# NixieClock_Modified2.net
KiCad netlist of a schematic drawn in EAGLE
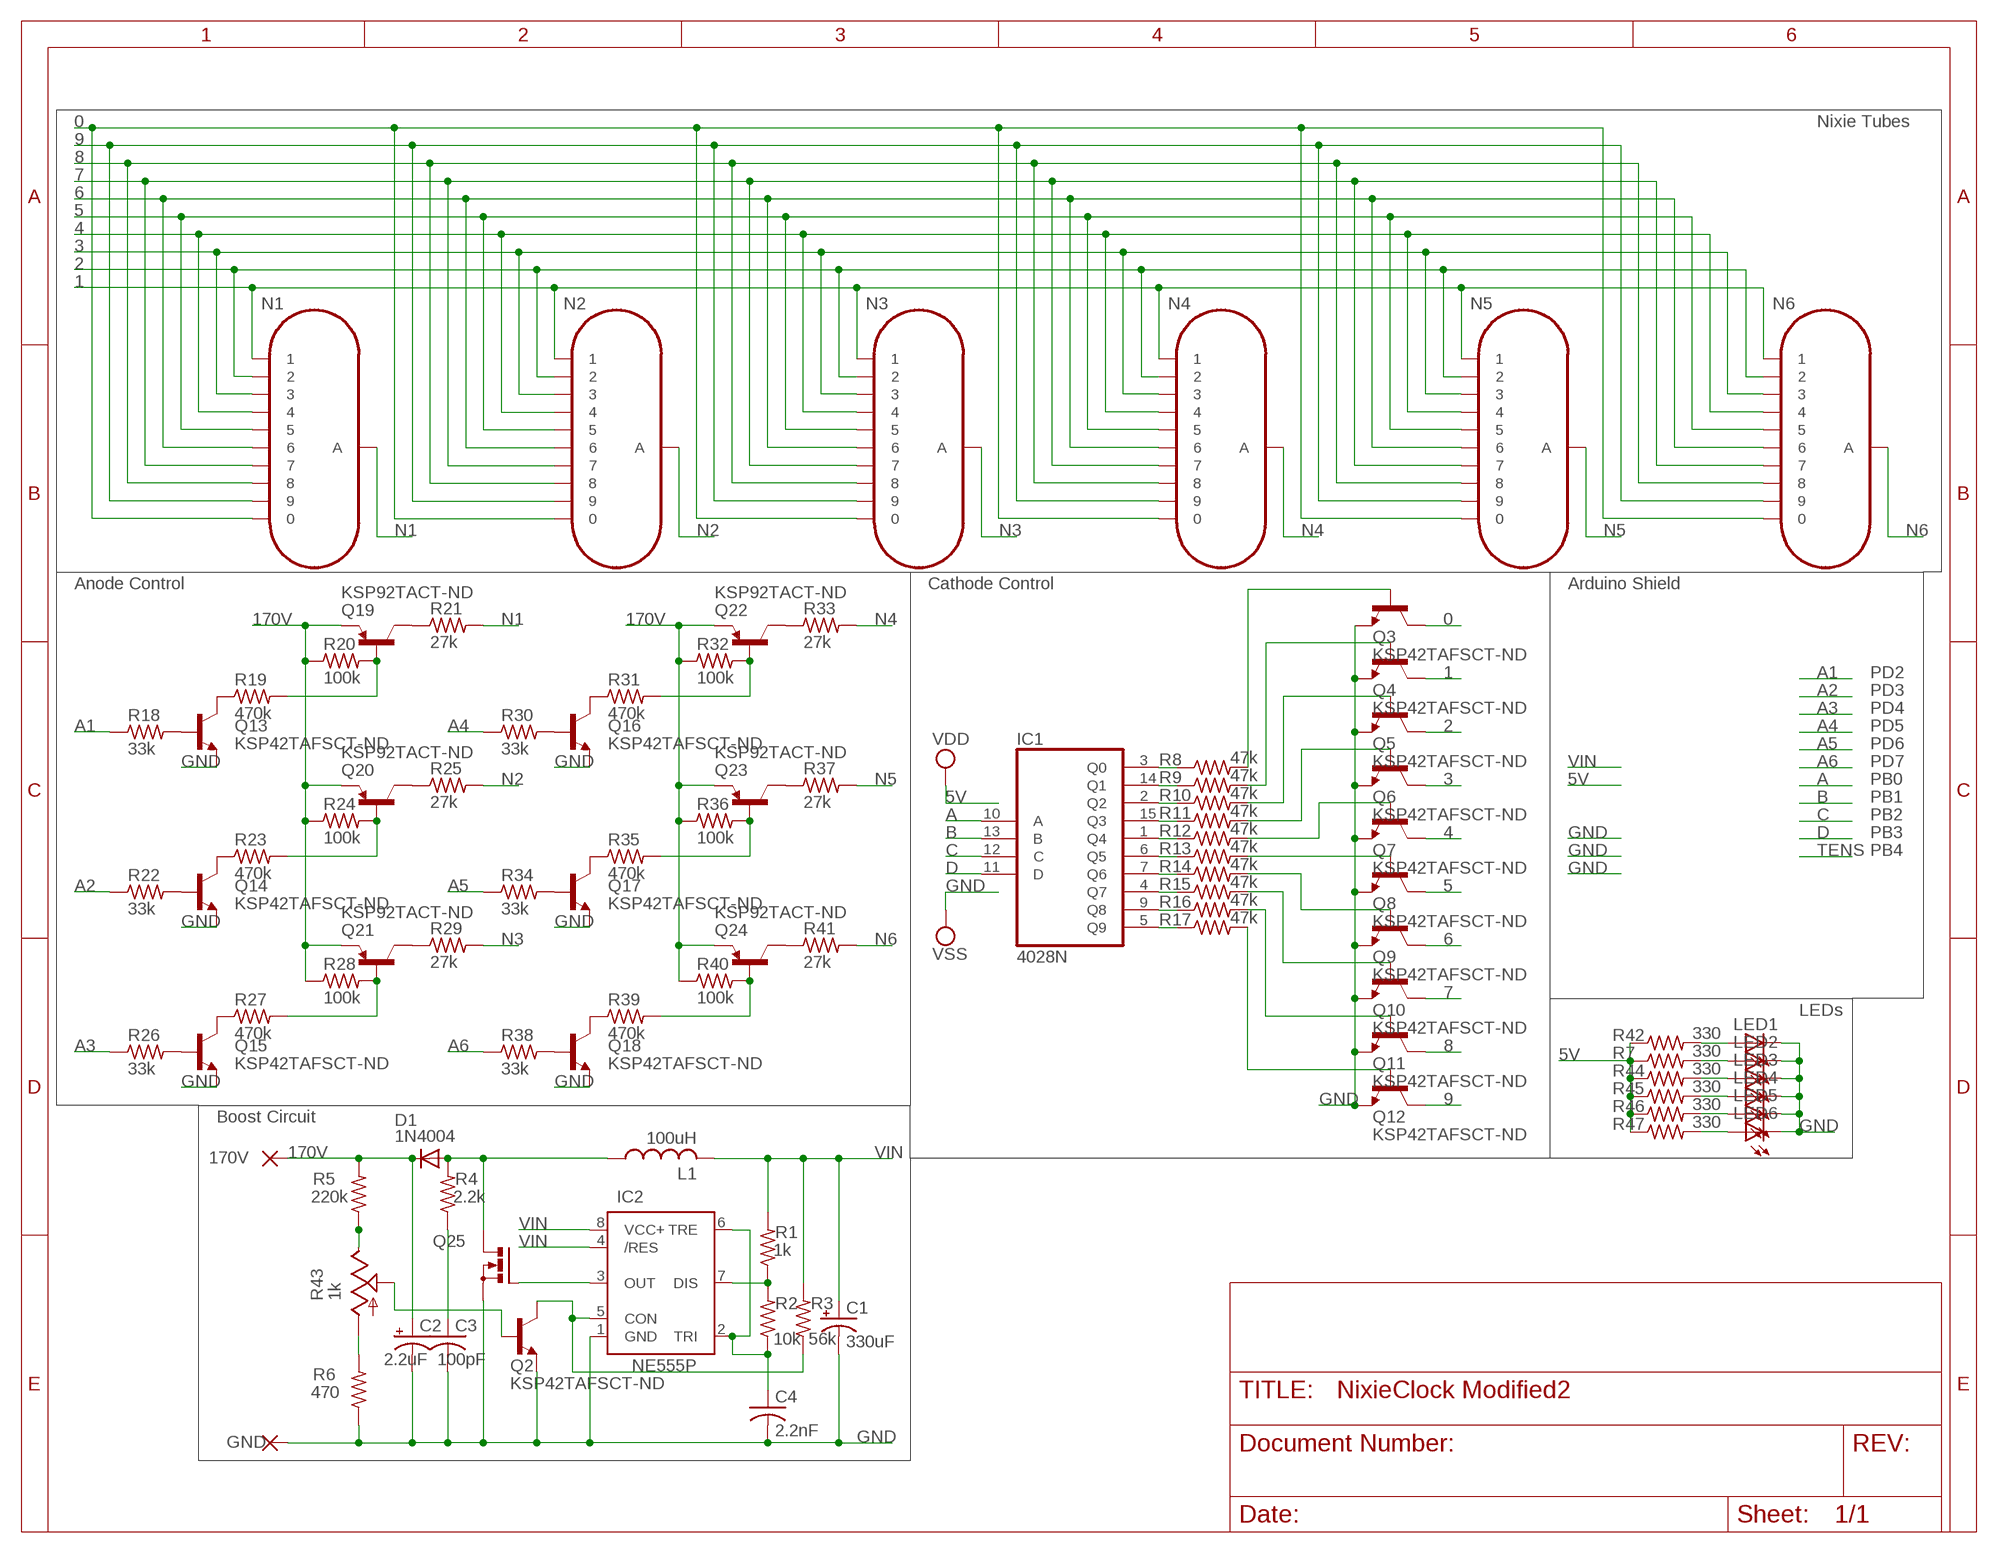
[diagram p0: schematic, sheet 1]

(export (version "E")
  (design (tool "Eeschema 10.0.6"))
  (components
    (comp (ref "C1")
      (value "330uF")
      (footprint "eagle-import:E2,5-6E")
      (libsource (lib "eagle-import") (part "CPOL-USE2,5-6E"))
    )
    (comp (ref "C2")
      (value "2.2uF")
      (footprint "eagle-import:E2,5-6E")
      (libsource (lib "eagle-import") (part "CPOL-USE2,5-6E"))
    )
    (comp (ref "C3")
      (value "100pF")
      (footprint "eagle-import:C050-025X075")
      (libsource (lib "eagle-import") (part "C-US050-025X075"))
    )
    (comp (ref "C4")
      (value "2.2nF")
      (footprint "eagle-import:C025-025X050")
      (libsource (lib "eagle-import") (part "resistor_C-US025-025X050"))
    )
    (comp (ref "D1")
      (value "1N4004")
      (footprint "eagle-import:DO41-10")
      (libsource (lib "eagle-import") (part "1N4004"))
    )
    (comp (ref "IC1")
      (value "4028N")
      (footprint "eagle-import:DIL16")
      (libsource (lib "eagle-import") (part "4028N"))
    )
    (comp (ref "IC2")
      (value "NE555P")
      (footprint "eagle-import:DIL-08")
      (fields (field (name "MF") "Arrow Electronics") (field (name "MPN") "NE555N"))
      (libsource (lib "eagle-import") (part "NE555P"))
    )
    (comp (ref "L1")
      (value "100uH")
      (footprint "eagle-import:6000-XXXX-RC")
      (libsource (lib "eagle-import") (part "L-US6000-XXX-RC"))
    )
    (comp (ref "LED1")
      (value "LEDCHIPLED_1206")
      (footprint "eagle-import:CHIPLED_1206")
      (libsource (lib "eagle-import") (part "LEDCHIPLED_1206"))
    )
    (comp (ref "LED2")
      (value "LEDCHIPLED_1206")
      (footprint "eagle-import:CHIPLED_1206")
      (libsource (lib "eagle-import") (part "LEDCHIPLED_1206"))
    )
    (comp (ref "LED3")
      (value "LEDCHIPLED_1206")
      (footprint "eagle-import:CHIPLED_1206")
      (libsource (lib "eagle-import") (part "LEDCHIPLED_1206"))
    )
    (comp (ref "LED4")
      (value "LEDCHIPLED_1206")
      (footprint "eagle-import:CHIPLED_1206")
      (libsource (lib "eagle-import") (part "LEDCHIPLED_1206"))
    )
    (comp (ref "LED5")
      (value "LEDCHIPLED_1206")
      (footprint "eagle-import:CHIPLED_1206")
      (libsource (lib "eagle-import") (part "LEDCHIPLED_1206"))
    )
    (comp (ref "LED6")
      (value "LEDCHIPLED_1206")
      (footprint "eagle-import:CHIPLED_1206")
      (libsource (lib "eagle-import") (part "LEDCHIPLED_1206"))
    )
    (comp (ref "N1")
      (value "IN-17")
      (footprint "eagle-import:IN-17")
      (libsource (lib "eagle-import") (part "IN-17"))
    )
    (comp (ref "N2")
      (value "IN-17")
      (footprint "eagle-import:IN-17")
      (libsource (lib "eagle-import") (part "IN-17"))
    )
    (comp (ref "N3")
      (value "IN-17")
      (footprint "eagle-import:IN-17")
      (libsource (lib "eagle-import") (part "IN-17"))
    )
    (comp (ref "N4")
      (value "IN-17")
      (footprint "eagle-import:IN-17")
      (libsource (lib "eagle-import") (part "IN-17"))
    )
    (comp (ref "N5")
      (value "IN-17")
      (footprint "eagle-import:IN-17")
      (libsource (lib "eagle-import") (part "IN-17"))
    )
    (comp (ref "N6")
      (value "IN-17")
      (footprint "eagle-import:IN-17")
      (libsource (lib "eagle-import") (part "IN-17"))
    )
    (comp (ref "PAD13")
      (value "GND")
      (footprint "eagle-import:1,6_0,8")
      (libsource (lib "eagle-import") (part "1,6/0,8"))
    )
    (comp (ref "PAD14")
      (value "170V")
      (footprint "eagle-import:1,6_0,8")
      (libsource (lib "eagle-import") (part "1,6/0,8"))
    )
    (comp (ref "Q2")
      (value "KSP42TAFSCT-ND")
      (footprint "eagle-import:TO-92-AMMO")
      (libsource (lib "eagle-import") (part "TRANSISTOR_NPNTO-92-AMMO"))
    )
    (comp (ref "Q3")
      (value "KSP42TAFSCT-ND")
      (footprint "eagle-import:TO-92-AMMO")
      (libsource (lib "eagle-import") (part "TRANSISTOR_NPNTO-92-AMMO"))
    )
    (comp (ref "Q4")
      (value "KSP42TAFSCT-ND")
      (footprint "eagle-import:TO-92-AMMO")
      (libsource (lib "eagle-import") (part "TRANSISTOR_NPNTO-92-AMMO"))
    )
    (comp (ref "Q5")
      (value "KSP42TAFSCT-ND")
      (footprint "eagle-import:TO-92-AMMO")
      (libsource (lib "eagle-import") (part "TRANSISTOR_NPNTO-92-AMMO"))
    )
    (comp (ref "Q6")
      (value "KSP42TAFSCT-ND")
      (footprint "eagle-import:TO-92-AMMO")
      (libsource (lib "eagle-import") (part "TRANSISTOR_NPNTO-92-AMMO"))
    )
    (comp (ref "Q7")
      (value "KSP42TAFSCT-ND")
      (footprint "eagle-import:TO-92-AMMO")
      (libsource (lib "eagle-import") (part "TRANSISTOR_NPNTO-92-AMMO"))
    )
    (comp (ref "Q8")
      (value "KSP42TAFSCT-ND")
      (footprint "eagle-import:TO-92-AMMO")
      (libsource (lib "eagle-import") (part "TRANSISTOR_NPNTO-92-AMMO"))
    )
    (comp (ref "Q9")
      (value "KSP42TAFSCT-ND")
      (footprint "eagle-import:TO-92-AMMO")
      (libsource (lib "eagle-import") (part "TRANSISTOR_NPNTO-92-AMMO"))
    )
    (comp (ref "Q10")
      (value "KSP42TAFSCT-ND")
      (footprint "eagle-import:TO-92-AMMO")
      (libsource (lib "eagle-import") (part "TRANSISTOR_NPNTO-92-AMMO"))
    )
    (comp (ref "Q11")
      (value "KSP42TAFSCT-ND")
      (footprint "eagle-import:TO-92-AMMO")
      (libsource (lib "eagle-import") (part "TRANSISTOR_NPNTO-92-AMMO"))
    )
    (comp (ref "Q12")
      (value "KSP42TAFSCT-ND")
      (footprint "eagle-import:TO-92-AMMO")
      (libsource (lib "eagle-import") (part "TRANSISTOR_NPNTO-92-AMMO"))
    )
    (comp (ref "Q13")
      (value "KSP42TAFSCT-ND")
      (footprint "eagle-import:TO-92-AMMO")
      (libsource (lib "eagle-import") (part "TRANSISTOR_NPNTO-92-AMMO"))
    )
    (comp (ref "Q14")
      (value "KSP42TAFSCT-ND")
      (footprint "eagle-import:TO-92-AMMO")
      (libsource (lib "eagle-import") (part "TRANSISTOR_NPNTO-92-AMMO"))
    )
    (comp (ref "Q15")
      (value "KSP42TAFSCT-ND")
      (footprint "eagle-import:TO-92-AMMO")
      (libsource (lib "eagle-import") (part "TRANSISTOR_NPNTO-92-AMMO"))
    )
    (comp (ref "Q16")
      (value "KSP42TAFSCT-ND")
      (footprint "eagle-import:TO-92-AMMO")
      (libsource (lib "eagle-import") (part "TRANSISTOR_NPNTO-92-AMMO"))
    )
    (comp (ref "Q17")
      (value "KSP42TAFSCT-ND")
      (footprint "eagle-import:TO-92-AMMO")
      (libsource (lib "eagle-import") (part "TRANSISTOR_NPNTO-92-AMMO"))
    )
    (comp (ref "Q18")
      (value "KSP42TAFSCT-ND")
      (footprint "eagle-import:TO-92-AMMO")
      (libsource (lib "eagle-import") (part "TRANSISTOR_NPNTO-92-AMMO"))
    )
    (comp (ref "Q19")
      (value "KSP92TACT-ND")
      (footprint "eagle-import:TO-92-AMMO")
      (libsource (lib "eagle-import") (part "TRANSISTOR_PNP"))
    )
    (comp (ref "Q20")
      (value "KSP92TACT-ND")
      (footprint "eagle-import:TO-92-AMMO")
      (libsource (lib "eagle-import") (part "TRANSISTOR_PNP"))
    )
    (comp (ref "Q21")
      (value "KSP92TACT-ND")
      (footprint "eagle-import:TO-92-AMMO")
      (libsource (lib "eagle-import") (part "TRANSISTOR_PNP"))
    )
    (comp (ref "Q22")
      (value "KSP92TACT-ND")
      (footprint "eagle-import:TO-92-AMMO")
      (libsource (lib "eagle-import") (part "TRANSISTOR_PNP"))
    )
    (comp (ref "Q23")
      (value "KSP92TACT-ND")
      (footprint "eagle-import:TO-92-AMMO")
      (libsource (lib "eagle-import") (part "TRANSISTOR_PNP"))
    )
    (comp (ref "Q24")
      (value "KSP92TACT-ND")
      (footprint "eagle-import:TO-92-AMMO")
      (libsource (lib "eagle-import") (part "TRANSISTOR_PNP"))
    )
    (comp (ref "Q25")
      (value "PMOSFET_NTO220BH")
      (footprint "eagle-import:TO220BH")
      (libsource (lib "eagle-import") (part "PMOSFET_NTO220BH"))
    )
    (comp (ref "R1")
      (value "1k")
      (footprint "eagle-import:0204_5")
      (libsource (lib "eagle-import") (part "R-US_0204/5"))
    )
    (comp (ref "R2")
      (value "10k")
      (footprint "eagle-import:0204_5")
      (libsource (lib "eagle-import") (part "R-US_0204/5"))
    )
    (comp (ref "R3")
      (value "56k")
      (footprint "eagle-import:0204_5")
      (libsource (lib "eagle-import") (part "R-US_0204/5"))
    )
    (comp (ref "R4")
      (value "2.2k")
      (footprint "eagle-import:0204_5")
      (libsource (lib "eagle-import") (part "R-US_0204/5"))
    )
    (comp (ref "R5")
      (value "220k")
      (footprint "eagle-import:0204_5")
      (libsource (lib "eagle-import") (part "R-US_0204/5"))
    )
    (comp (ref "R6")
      (value "470")
      (footprint "eagle-import:0204_5")
      (libsource (lib "eagle-import") (part "R-US_0204/5"))
    )
    (comp (ref "R7")
      (value "330")
      (footprint "eagle-import:0204_5")
      (libsource (lib "eagle-import") (part "R-US_0204/5"))
    )
    (comp (ref "R8")
      (value "47k")
      (footprint "eagle-import:0204_5")
      (libsource (lib "eagle-import") (part "R-US_0204/5"))
    )
    (comp (ref "R9")
      (value "47k")
      (footprint "eagle-import:0204_5")
      (libsource (lib "eagle-import") (part "R-US_0204/5"))
    )
    (comp (ref "R10")
      (value "47k")
      (footprint "eagle-import:0204_5")
      (libsource (lib "eagle-import") (part "R-US_0204/5"))
    )
    (comp (ref "R11")
      (value "47k")
      (footprint "eagle-import:0204_5")
      (libsource (lib "eagle-import") (part "R-US_0204/5"))
    )
    (comp (ref "R12")
      (value "47k")
      (footprint "eagle-import:0204_5")
      (libsource (lib "eagle-import") (part "R-US_0204/5"))
    )
    (comp (ref "R13")
      (value "47k")
      (footprint "eagle-import:0204_5")
      (libsource (lib "eagle-import") (part "R-US_0204/5"))
    )
    (comp (ref "R14")
      (value "47k")
      (footprint "eagle-import:0204_5")
      (libsource (lib "eagle-import") (part "R-US_0204/5"))
    )
    (comp (ref "R15")
      (value "47k")
      (footprint "eagle-import:0204_5")
      (libsource (lib "eagle-import") (part "R-US_0204/5"))
    )
    (comp (ref "R16")
      (value "47k")
      (footprint "eagle-import:0204_5")
      (libsource (lib "eagle-import") (part "R-US_0204/5"))
    )
    (comp (ref "R17")
      (value "47k")
      (footprint "eagle-import:0204_5")
      (libsource (lib "eagle-import") (part "R-US_0204/5"))
    )
    (comp (ref "R18")
      (value "33k")
      (footprint "eagle-import:0204_5")
      (libsource (lib "eagle-import") (part "R-US_0204/5"))
    )
    (comp (ref "R19")
      (value "470k")
      (footprint "eagle-import:0204_5")
      (libsource (lib "eagle-import") (part "R-US_0204/5"))
    )
    (comp (ref "R20")
      (value "100k")
      (footprint "eagle-import:0204_5")
      (libsource (lib "eagle-import") (part "R-US_0204/5"))
    )
    (comp (ref "R21")
      (value "27k")
      (footprint "eagle-import:0204_5")
      (libsource (lib "eagle-import") (part "R-US_0204/5"))
    )
    (comp (ref "R22")
      (value "33k")
      (footprint "eagle-import:0204_5")
      (libsource (lib "eagle-import") (part "R-US_0204/5"))
    )
    (comp (ref "R23")
      (value "470k")
      (footprint "eagle-import:0204_5")
      (libsource (lib "eagle-import") (part "R-US_0204/5"))
    )
    (comp (ref "R24")
      (value "100k")
      (footprint "eagle-import:0204_5")
      (libsource (lib "eagle-import") (part "R-US_0204/5"))
    )
    (comp (ref "R25")
      (value "27k")
      (footprint "eagle-import:0204_5")
      (libsource (lib "eagle-import") (part "R-US_0204/5"))
    )
    (comp (ref "R26")
      (value "33k")
      (footprint "eagle-import:0204_5")
      (libsource (lib "eagle-import") (part "R-US_0204/5"))
    )
    (comp (ref "R27")
      (value "470k")
      (footprint "eagle-import:0204_5")
      (libsource (lib "eagle-import") (part "R-US_0204/5"))
    )
    (comp (ref "R28")
      (value "100k")
      (footprint "eagle-import:0204_5")
      (libsource (lib "eagle-import") (part "R-US_0204/5"))
    )
    (comp (ref "R29")
      (value "27k")
      (footprint "eagle-import:0204_5")
      (libsource (lib "eagle-import") (part "R-US_0204/5"))
    )
    (comp (ref "R30")
      (value "33k")
      (footprint "eagle-import:0204_5")
      (libsource (lib "eagle-import") (part "R-US_0204/5"))
    )
    (comp (ref "R31")
      (value "470k")
      (footprint "eagle-import:0204_5")
      (libsource (lib "eagle-import") (part "R-US_0204/5"))
    )
    (comp (ref "R32")
      (value "100k")
      (footprint "eagle-import:0204_5")
      (libsource (lib "eagle-import") (part "R-US_0204/5"))
    )
    (comp (ref "R33")
      (value "27k")
      (footprint "eagle-import:0204_5")
      (libsource (lib "eagle-import") (part "R-US_0204/5"))
    )
    (comp (ref "R34")
      (value "33k")
      (footprint "eagle-import:0204_5")
      (libsource (lib "eagle-import") (part "R-US_0204/5"))
    )
    (comp (ref "R35")
      (value "470k")
      (footprint "eagle-import:0204_5")
      (libsource (lib "eagle-import") (part "R-US_0204/5"))
    )
    (comp (ref "R36")
      (value "100k")
      (footprint "eagle-import:0204_5")
      (libsource (lib "eagle-import") (part "R-US_0204/5"))
    )
    (comp (ref "R37")
      (value "27k")
      (footprint "eagle-import:0204_5")
      (libsource (lib "eagle-import") (part "R-US_0204/5"))
    )
    (comp (ref "R38")
      (value "33k")
      (footprint "eagle-import:0204_5")
      (libsource (lib "eagle-import") (part "R-US_0204/5"))
    )
    (comp (ref "R39")
      (value "470k")
      (footprint "eagle-import:0204_5")
      (libsource (lib "eagle-import") (part "R-US_0204/5"))
    )
    (comp (ref "R40")
      (value "100k")
      (footprint "eagle-import:0204_5")
      (libsource (lib "eagle-import") (part "R-US_0204/5"))
    )
    (comp (ref "R41")
      (value "27k")
      (footprint "eagle-import:0204_5")
      (libsource (lib "eagle-import") (part "R-US_0204/5"))
    )
    (comp (ref "R42")
      (value "330")
      (footprint "eagle-import:0204_5")
      (libsource (lib "eagle-import") (part "R-US_0204/5"))
    )
    (comp (ref "R43")
      (value "1k")
      (footprint "eagle-import:B64Y")
      (libsource (lib "eagle-import") (part "TRIM_US-B64Y"))
    )
    (comp (ref "R44")
      (value "330")
      (footprint "eagle-import:0204_5")
      (libsource (lib "eagle-import") (part "R-US_0204/5"))
    )
    (comp (ref "R45")
      (value "330")
      (footprint "eagle-import:0204_5")
      (libsource (lib "eagle-import") (part "R-US_0204/5"))
    )
    (comp (ref "R46")
      (value "330")
      (footprint "eagle-import:0204_5")
      (libsource (lib "eagle-import") (part "R-US_0204/5"))
    )
    (comp (ref "R47")
      (value "330")
      (footprint "eagle-import:0204_5")
      (libsource (lib "eagle-import") (part "R-US_0204/5"))
    )
  )
  (nets
    (net (code "1") (name "/0") (class "Default")
      (node (ref "N1") (pin "0") (pinfunction "0_0") (pintype "bidirectional"))
      (node (ref "N2") (pin "0") (pinfunction "0_0") (pintype "bidirectional"))
      (node (ref "N3") (pin "0") (pinfunction "0_0") (pintype "bidirectional"))
      (node (ref "N4") (pin "0") (pinfunction "0_0") (pintype "bidirectional"))
      (node (ref "N5") (pin "0") (pinfunction "0_0") (pintype "bidirectional"))
      (node (ref "N6") (pin "0") (pinfunction "0_0") (pintype "bidirectional"))
      (node (ref "Q3") (pin "3") (pinfunction "C_3") (pintype "passive"))
    )
    (net (code "2") (name "/1") (class "Default")
      (node (ref "N1") (pin "1") (pinfunction "1_1") (pintype "bidirectional"))
      (node (ref "N2") (pin "1") (pinfunction "1_1") (pintype "bidirectional"))
      (node (ref "N3") (pin "1") (pinfunction "1_1") (pintype "bidirectional"))
      (node (ref "N4") (pin "1") (pinfunction "1_1") (pintype "bidirectional"))
      (node (ref "N5") (pin "1") (pinfunction "1_1") (pintype "bidirectional"))
      (node (ref "N6") (pin "1") (pinfunction "1_1") (pintype "bidirectional"))
      (node (ref "Q4") (pin "3") (pinfunction "C_3") (pintype "passive"))
    )
    (net (code "3") (name "/2") (class "Default")
      (node (ref "N1") (pin "2") (pinfunction "2_2") (pintype "bidirectional"))
      (node (ref "N2") (pin "2") (pinfunction "2_2") (pintype "bidirectional"))
      (node (ref "N3") (pin "2") (pinfunction "2_2") (pintype "bidirectional"))
      (node (ref "N4") (pin "2") (pinfunction "2_2") (pintype "bidirectional"))
      (node (ref "N5") (pin "2") (pinfunction "2_2") (pintype "bidirectional"))
      (node (ref "N6") (pin "2") (pinfunction "2_2") (pintype "bidirectional"))
      (node (ref "Q5") (pin "3") (pinfunction "C_3") (pintype "passive"))
    )
    (net (code "4") (name "/3") (class "Default")
      (node (ref "N1") (pin "3") (pinfunction "3_3") (pintype "bidirectional"))
      (node (ref "N2") (pin "3") (pinfunction "3_3") (pintype "bidirectional"))
      (node (ref "N3") (pin "3") (pinfunction "3_3") (pintype "bidirectional"))
      (node (ref "N4") (pin "3") (pinfunction "3_3") (pintype "bidirectional"))
      (node (ref "N5") (pin "3") (pinfunction "3_3") (pintype "bidirectional"))
      (node (ref "N6") (pin "3") (pinfunction "3_3") (pintype "bidirectional"))
      (node (ref "Q6") (pin "3") (pinfunction "C_3") (pintype "passive"))
    )
    (net (code "5") (name "/4") (class "Default")
      (node (ref "N1") (pin "4") (pinfunction "4_4") (pintype "bidirectional"))
      (node (ref "N2") (pin "4") (pinfunction "4_4") (pintype "bidirectional"))
      (node (ref "N3") (pin "4") (pinfunction "4_4") (pintype "bidirectional"))
      (node (ref "N4") (pin "4") (pinfunction "4_4") (pintype "bidirectional"))
      (node (ref "N5") (pin "4") (pinfunction "4_4") (pintype "bidirectional"))
      (node (ref "N6") (pin "4") (pinfunction "4_4") (pintype "bidirectional"))
      (node (ref "Q7") (pin "3") (pinfunction "C_3") (pintype "passive"))
    )
    (net (code "6") (name "/5") (class "Default")
      (node (ref "N1") (pin "5") (pinfunction "5_5") (pintype "bidirectional"))
      (node (ref "N2") (pin "5") (pinfunction "5_5") (pintype "bidirectional"))
      (node (ref "N3") (pin "5") (pinfunction "5_5") (pintype "bidirectional"))
      (node (ref "N4") (pin "5") (pinfunction "5_5") (pintype "bidirectional"))
      (node (ref "N5") (pin "5") (pinfunction "5_5") (pintype "bidirectional"))
      (node (ref "N6") (pin "5") (pinfunction "5_5") (pintype "bidirectional"))
      (node (ref "Q8") (pin "3") (pinfunction "C_3") (pintype "passive"))
    )
    (net (code "7") (name "/6") (class "Default")
      (node (ref "N1") (pin "6") (pinfunction "6_6") (pintype "bidirectional"))
      (node (ref "N2") (pin "6") (pinfunction "6_6") (pintype "bidirectional"))
      (node (ref "N3") (pin "6") (pinfunction "6_6") (pintype "bidirectional"))
      (node (ref "N4") (pin "6") (pinfunction "6_6") (pintype "bidirectional"))
      (node (ref "N5") (pin "6") (pinfunction "6_6") (pintype "bidirectional"))
      (node (ref "N6") (pin "6") (pinfunction "6_6") (pintype "bidirectional"))
      (node (ref "Q9") (pin "3") (pinfunction "C_3") (pintype "passive"))
    )
    (net (code "8") (name "/7") (class "Default")
      (node (ref "N1") (pin "7") (pinfunction "7_7") (pintype "bidirectional"))
      (node (ref "N2") (pin "7") (pinfunction "7_7") (pintype "bidirectional"))
      (node (ref "N3") (pin "7") (pinfunction "7_7") (pintype "bidirectional"))
      (node (ref "N4") (pin "7") (pinfunction "7_7") (pintype "bidirectional"))
      (node (ref "N5") (pin "7") (pinfunction "7_7") (pintype "bidirectional"))
      (node (ref "N6") (pin "7") (pinfunction "7_7") (pintype "bidirectional"))
      (node (ref "Q10") (pin "3") (pinfunction "C_3") (pintype "passive"))
    )
    (net (code "9") (name "/8") (class "Default")
      (node (ref "N1") (pin "8") (pinfunction "8_8") (pintype "bidirectional"))
      (node (ref "N2") (pin "8") (pinfunction "8_8") (pintype "bidirectional"))
      (node (ref "N3") (pin "8") (pinfunction "8_8") (pintype "bidirectional"))
      (node (ref "N4") (pin "8") (pinfunction "8_8") (pintype "bidirectional"))
      (node (ref "N5") (pin "8") (pinfunction "8_8") (pintype "bidirectional"))
      (node (ref "N6") (pin "8") (pinfunction "8_8") (pintype "bidirectional"))
      (node (ref "Q11") (pin "3") (pinfunction "C_3") (pintype "passive"))
    )
    (net (code "10") (name "/9") (class "Default")
      (node (ref "N1") (pin "9") (pinfunction "9_9") (pintype "bidirectional"))
      (node (ref "N2") (pin "9") (pinfunction "9_9") (pintype "bidirectional"))
      (node (ref "N3") (pin "9") (pinfunction "9_9") (pintype "bidirectional"))
      (node (ref "N4") (pin "9") (pinfunction "9_9") (pintype "bidirectional"))
      (node (ref "N5") (pin "9") (pinfunction "9_9") (pintype "bidirectional"))
      (node (ref "N6") (pin "9") (pinfunction "9_9") (pintype "bidirectional"))
      (node (ref "Q12") (pin "3") (pinfunction "C_3") (pintype "passive"))
    )
    (net (code "11") (name "/170V") (class "Default")
      (node (ref "C2") (pin "+") (pinfunction "+_+") (pintype "passive"))
      (node (ref "D1") (pin "C") (pinfunction "C_C") (pintype "passive"))
      (node (ref "PAD14") (pin "1") (pinfunction "P_1") (pintype "passive"))
      (node (ref "Q19") (pin "1") (pinfunction "E_1") (pintype "passive"))
      (node (ref "Q20") (pin "1") (pinfunction "E_1") (pintype "passive"))
      (node (ref "Q21") (pin "1") (pinfunction "E_1") (pintype "passive"))
      (node (ref "Q22") (pin "1") (pinfunction "E_1") (pintype "passive"))
      (node (ref "Q23") (pin "1") (pinfunction "E_1") (pintype "passive"))
      (node (ref "Q24") (pin "1") (pinfunction "E_1") (pintype "passive"))
      (node (ref "R20") (pin "1") (pinfunction "1_1") (pintype "passive"))
      (node (ref "R24") (pin "1") (pinfunction "1_1") (pintype "passive"))
      (node (ref "R28") (pin "1") (pinfunction "1_1") (pintype "passive"))
      (node (ref "R32") (pin "1") (pinfunction "1_1") (pintype "passive"))
      (node (ref "R36") (pin "1") (pinfunction "1_1") (pintype "passive"))
      (node (ref "R40") (pin "1") (pinfunction "1_1") (pintype "passive"))
      (node (ref "R5") (pin "2") (pinfunction "2_2") (pintype "passive"))
    )
    (net (code "12") (name "/A") (class "Default")
      (node (ref "IC1") (pin "10") (pinfunction "A_10") (pintype "input"))
    )
    (net (code "13") (name "/A1") (class "Default")
      (node (ref "R18") (pin "1") (pinfunction "1_1") (pintype "passive"))
    )
    (net (code "14") (name "/A2") (class "Default")
      (node (ref "R22") (pin "1") (pinfunction "1_1") (pintype "passive"))
    )
    (net (code "15") (name "/A3") (class "Default")
      (node (ref "R26") (pin "1") (pinfunction "1_1") (pintype "passive"))
    )
    (net (code "16") (name "/A4") (class "Default")
      (node (ref "R30") (pin "1") (pinfunction "1_1") (pintype "passive"))
    )
    (net (code "17") (name "/A5") (class "Default")
      (node (ref "R34") (pin "1") (pinfunction "1_1") (pintype "passive"))
    )
    (net (code "18") (name "/A6") (class "Default")
      (node (ref "R38") (pin "1") (pinfunction "1_1") (pintype "passive"))
    )
    (net (code "19") (name "/B") (class "Default")
      (node (ref "IC1") (pin "13") (pinfunction "B_13") (pintype "input"))
    )
    (net (code "20") (name "/C") (class "Default")
      (node (ref "IC1") (pin "12") (pinfunction "C_12") (pintype "input"))
    )
    (net (code "21") (name "/D") (class "Default")
      (node (ref "IC1") (pin "11") (pinfunction "D_11") (pintype "input"))
    )
    (net (code "22") (name "/N1") (class "Default")
      (node (ref "N1") (pin "A") (pinfunction "A_A") (pintype "bidirectional"))
      (node (ref "R21") (pin "2") (pinfunction "2_2") (pintype "passive"))
    )
    (net (code "23") (name "/N2") (class "Default")
      (node (ref "N2") (pin "A") (pinfunction "A_A") (pintype "bidirectional"))
      (node (ref "R25") (pin "2") (pinfunction "2_2") (pintype "passive"))
    )
    (net (code "24") (name "/N3") (class "Default")
      (node (ref "N3") (pin "A") (pinfunction "A_A") (pintype "bidirectional"))
      (node (ref "R29") (pin "2") (pinfunction "2_2") (pintype "passive"))
    )
    (net (code "25") (name "/N4") (class "Default")
      (node (ref "N4") (pin "A") (pinfunction "A_A") (pintype "bidirectional"))
      (node (ref "R33") (pin "2") (pinfunction "2_2") (pintype "passive"))
    )
    (net (code "26") (name "/N5") (class "Default")
      (node (ref "N5") (pin "A") (pinfunction "A_A") (pintype "bidirectional"))
      (node (ref "R37") (pin "2") (pinfunction "2_2") (pintype "passive"))
    )
    (net (code "27") (name "/N6") (class "Default")
      (node (ref "N6") (pin "A") (pinfunction "A_A") (pintype "bidirectional"))
      (node (ref "R41") (pin "2") (pinfunction "2_2") (pintype "passive"))
    )
    (net (code "29") (name "/VIN") (class "Default")
      (node (ref "C1") (pin "+") (pinfunction "+_+") (pintype "passive"))
      (node (ref "IC2") (pin "4") (pinfunction "/RES_4") (pintype "input"))
      (node (ref "IC2") (pin "8") (pinfunction "VCC+_8") (pintype "power_in"))
      (node (ref "L1") (pin "2") (pinfunction "2_2") (pintype "passive"))
      (node (ref "R1") (pin "2") (pinfunction "2_2") (pintype "passive"))
      (node (ref "R3") (pin "2") (pinfunction "2_2") (pintype "passive"))
    )
    (net (code "30") (name "Net-(C3-Pad1)") (class "Default")
      (node (ref "C3") (pin "1") (pinfunction "1_1") (pintype "passive"))
      (node (ref "R4") (pin "1") (pinfunction "1_1") (pintype "passive"))
    )
    (net (code "31") (name "Net-(D1-PadA)") (class "Default")
      (node (ref "D1") (pin "A") (pinfunction "A_A") (pintype "passive"))
      (node (ref "L1") (pin "1") (pinfunction "1_1") (pintype "passive"))
      (node (ref "Q25") (pin "D") (pinfunction "D_D") (pintype "passive"))
      (node (ref "R4") (pin "2") (pinfunction "2_2") (pintype "passive"))
    )
    (net (code "32") (name "Net-(IC1A-Q0)") (class "Default")
      (node (ref "IC1") (pin "3") (pinfunction "Q0_3") (pintype "output"))
      (node (ref "R8") (pin "1") (pinfunction "1_1") (pintype "passive"))
    )
    (net (code "33") (name "Net-(IC1A-Q1)") (class "Default")
      (node (ref "IC1") (pin "14") (pinfunction "Q1_14") (pintype "output"))
      (node (ref "R9") (pin "1") (pinfunction "1_1") (pintype "passive"))
    )
    (net (code "34") (name "Net-(IC1A-Q2)") (class "Default")
      (node (ref "IC1") (pin "2") (pinfunction "Q2_2") (pintype "output"))
      (node (ref "R10") (pin "1") (pinfunction "1_1") (pintype "passive"))
    )
    (net (code "35") (name "Net-(IC1A-Q3)") (class "Default")
      (node (ref "IC1") (pin "15") (pinfunction "Q3_15") (pintype "output"))
      (node (ref "R11") (pin "1") (pinfunction "1_1") (pintype "passive"))
    )
    (net (code "36") (name "Net-(IC1A-Q4)") (class "Default")
      (node (ref "IC1") (pin "1") (pinfunction "Q4_1") (pintype "output"))
      (node (ref "R12") (pin "1") (pinfunction "1_1") (pintype "passive"))
    )
    (net (code "37") (name "Net-(IC1A-Q5)") (class "Default")
      (node (ref "IC1") (pin "6") (pinfunction "Q5_6") (pintype "output"))
      (node (ref "R13") (pin "1") (pinfunction "1_1") (pintype "passive"))
    )
    (net (code "38") (name "Net-(IC1A-Q6)") (class "Default")
      (node (ref "IC1") (pin "7") (pinfunction "Q6_7") (pintype "output"))
      (node (ref "R14") (pin "1") (pinfunction "1_1") (pintype "passive"))
    )
    (net (code "39") (name "Net-(IC1A-Q7)") (class "Default")
      (node (ref "IC1") (pin "4") (pinfunction "Q7_4") (pintype "output"))
      (node (ref "R15") (pin "1") (pinfunction "1_1") (pintype "passive"))
    )
    (net (code "40") (name "Net-(IC1A-Q8)") (class "Default")
      (node (ref "IC1") (pin "9") (pinfunction "Q8_9") (pintype "output"))
      (node (ref "R16") (pin "1") (pinfunction "1_1") (pintype "passive"))
    )
    (net (code "41") (name "Net-(IC1A-Q9)") (class "Default")
      (node (ref "IC1") (pin "5") (pinfunction "Q9_5") (pintype "output"))
      (node (ref "R17") (pin "1") (pinfunction "1_1") (pintype "passive"))
    )
    (net (code "42") (name "Net-(IC2-CON)") (class "Default")
      (node (ref "IC2") (pin "5") (pinfunction "CON_5") (pintype "input"))
      (node (ref "Q2") (pin "3") (pinfunction "C_3") (pintype "passive"))
      (node (ref "R3") (pin "1") (pinfunction "1_1") (pintype "passive"))
    )
    (net (code "43") (name "Net-(IC2-DIS)") (class "Default")
      (node (ref "IC2") (pin "7") (pinfunction "DIS_7") (pintype "input"))
      (node (ref "R1") (pin "1") (pinfunction "1_1") (pintype "passive"))
      (node (ref "R2") (pin "2") (pinfunction "2_2") (pintype "passive"))
    )
    (net (code "44") (name "Net-(IC2-OUT)") (class "Default")
      (node (ref "IC2") (pin "3") (pinfunction "OUT_3") (pintype "output"))
      (node (ref "Q25") (pin "G") (pinfunction "G_G") (pintype "passive"))
    )
    (net (code "45") (name "Net-(IC2-TRE)") (class "Default")
      (node (ref "C4") (pin "1") (pinfunction "1_1") (pintype "passive"))
      (node (ref "IC2") (pin "2") (pinfunction "TRI_2") (pintype "input"))
      (node (ref "IC2") (pin "6") (pinfunction "TRE_6") (pintype "input"))
      (node (ref "R2") (pin "1") (pinfunction "1_1") (pintype "passive"))
    )
    (net (code "46") (name "Net-(LED1-PadA)") (class "Default")
      (node (ref "LED1") (pin "A") (pinfunction "A_A") (pintype "passive"))
      (node (ref "R42") (pin "2") (pinfunction "2_2") (pintype "passive"))
    )
    (net (code "47") (name "Net-(LED2-PadA)") (class "Default")
      (node (ref "LED2") (pin "A") (pinfunction "A_A") (pintype "passive"))
      (node (ref "R7") (pin "2") (pinfunction "2_2") (pintype "passive"))
    )
    (net (code "48") (name "Net-(LED3-PadA)") (class "Default")
      (node (ref "LED3") (pin "A") (pinfunction "A_A") (pintype "passive"))
      (node (ref "R44") (pin "2") (pinfunction "2_2") (pintype "passive"))
    )
    (net (code "49") (name "Net-(LED4-PadA)") (class "Default")
      (node (ref "LED4") (pin "A") (pinfunction "A_A") (pintype "passive"))
      (node (ref "R45") (pin "2") (pinfunction "2_2") (pintype "passive"))
    )
    (net (code "50") (name "Net-(LED5-PadA)") (class "Default")
      (node (ref "LED5") (pin "A") (pinfunction "A_A") (pintype "passive"))
      (node (ref "R46") (pin "2") (pinfunction "2_2") (pintype "passive"))
    )
    (net (code "51") (name "Net-(LED6-PadA)") (class "Default")
      (node (ref "LED6") (pin "A") (pinfunction "A_A") (pintype "passive"))
      (node (ref "R47") (pin "2") (pinfunction "2_2") (pintype "passive"))
    )
    (net (code "52") (name "Net-(Q2-B)") (class "Default")
      (node (ref "Q2") (pin "2") (pinfunction "B_2") (pintype "passive"))
      (node (ref "R43") (pin "S") (pinfunction "S_S") (pintype "passive"))
    )
    (net (code "53") (name "Net-(Q3-B)") (class "Default")
      (node (ref "Q3") (pin "2") (pinfunction "B_2") (pintype "passive"))
      (node (ref "R8") (pin "2") (pinfunction "2_2") (pintype "passive"))
    )
    (net (code "54") (name "Net-(Q4-B)") (class "Default")
      (node (ref "Q4") (pin "2") (pinfunction "B_2") (pintype "passive"))
      (node (ref "R9") (pin "2") (pinfunction "2_2") (pintype "passive"))
    )
    (net (code "55") (name "Net-(Q5-B)") (class "Default")
      (node (ref "Q5") (pin "2") (pinfunction "B_2") (pintype "passive"))
      (node (ref "R10") (pin "2") (pinfunction "2_2") (pintype "passive"))
    )
    (net (code "56") (name "Net-(Q6-B)") (class "Default")
      (node (ref "Q6") (pin "2") (pinfunction "B_2") (pintype "passive"))
      (node (ref "R11") (pin "2") (pinfunction "2_2") (pintype "passive"))
    )
    (net (code "57") (name "Net-(Q7-B)") (class "Default")
      (node (ref "Q7") (pin "2") (pinfunction "B_2") (pintype "passive"))
      (node (ref "R12") (pin "2") (pinfunction "2_2") (pintype "passive"))
    )
    (net (code "58") (name "Net-(Q8-B)") (class "Default")
      (node (ref "Q8") (pin "2") (pinfunction "B_2") (pintype "passive"))
      (node (ref "R13") (pin "2") (pinfunction "2_2") (pintype "passive"))
    )
    (net (code "59") (name "Net-(Q9-B)") (class "Default")
      (node (ref "Q9") (pin "2") (pinfunction "B_2") (pintype "passive"))
      (node (ref "R14") (pin "2") (pinfunction "2_2") (pintype "passive"))
    )
    (net (code "60") (name "Net-(Q10-B)") (class "Default")
      (node (ref "Q10") (pin "2") (pinfunction "B_2") (pintype "passive"))
      (node (ref "R15") (pin "2") (pinfunction "2_2") (pintype "passive"))
    )
    (net (code "61") (name "Net-(Q11-B)") (class "Default")
      (node (ref "Q11") (pin "2") (pinfunction "B_2") (pintype "passive"))
      (node (ref "R16") (pin "2") (pinfunction "2_2") (pintype "passive"))
    )
    (net (code "62") (name "Net-(Q12-B)") (class "Default")
      (node (ref "Q12") (pin "2") (pinfunction "B_2") (pintype "passive"))
      (node (ref "R17") (pin "2") (pinfunction "2_2") (pintype "passive"))
    )
    (net (code "63") (name "Net-(Q13-B)") (class "Default")
      (node (ref "Q13") (pin "2") (pinfunction "B_2") (pintype "passive"))
      (node (ref "R18") (pin "2") (pinfunction "2_2") (pintype "passive"))
    )
    (net (code "64") (name "Net-(Q13-C)") (class "Default")
      (node (ref "Q13") (pin "3") (pinfunction "C_3") (pintype "passive"))
      (node (ref "R19") (pin "1") (pinfunction "1_1") (pintype "passive"))
    )
    (net (code "65") (name "Net-(Q14-B)") (class "Default")
      (node (ref "Q14") (pin "2") (pinfunction "B_2") (pintype "passive"))
      (node (ref "R22") (pin "2") (pinfunction "2_2") (pintype "passive"))
    )
    (net (code "66") (name "Net-(Q14-C)") (class "Default")
      (node (ref "Q14") (pin "3") (pinfunction "C_3") (pintype "passive"))
      (node (ref "R23") (pin "1") (pinfunction "1_1") (pintype "passive"))
    )
    (net (code "67") (name "Net-(Q15-B)") (class "Default")
      (node (ref "Q15") (pin "2") (pinfunction "B_2") (pintype "passive"))
      (node (ref "R26") (pin "2") (pinfunction "2_2") (pintype "passive"))
    )
    (net (code "68") (name "Net-(Q15-C)") (class "Default")
      (node (ref "Q15") (pin "3") (pinfunction "C_3") (pintype "passive"))
      (node (ref "R27") (pin "1") (pinfunction "1_1") (pintype "passive"))
    )
    (net (code "69") (name "Net-(Q16-B)") (class "Default")
      (node (ref "Q16") (pin "2") (pinfunction "B_2") (pintype "passive"))
      (node (ref "R30") (pin "2") (pinfunction "2_2") (pintype "passive"))
    )
    (net (code "70") (name "Net-(Q16-C)") (class "Default")
      (node (ref "Q16") (pin "3") (pinfunction "C_3") (pintype "passive"))
      (node (ref "R31") (pin "1") (pinfunction "1_1") (pintype "passive"))
    )
    (net (code "71") (name "Net-(Q17-B)") (class "Default")
      (node (ref "Q17") (pin "2") (pinfunction "B_2") (pintype "passive"))
      (node (ref "R34") (pin "2") (pinfunction "2_2") (pintype "passive"))
    )
    (net (code "72") (name "Net-(Q17-C)") (class "Default")
      (node (ref "Q17") (pin "3") (pinfunction "C_3") (pintype "passive"))
      (node (ref "R35") (pin "1") (pinfunction "1_1") (pintype "passive"))
    )
    (net (code "73") (name "Net-(Q18-B)") (class "Default")
      (node (ref "Q18") (pin "2") (pinfunction "B_2") (pintype "passive"))
      (node (ref "R38") (pin "2") (pinfunction "2_2") (pintype "passive"))
    )
    (net (code "74") (name "Net-(Q18-C)") (class "Default")
      (node (ref "Q18") (pin "3") (pinfunction "C_3") (pintype "passive"))
      (node (ref "R39") (pin "1") (pinfunction "1_1") (pintype "passive"))
    )
    (net (code "75") (name "Net-(Q19-B)") (class "Default")
      (node (ref "Q19") (pin "2") (pinfunction "B_2") (pintype "passive"))
      (node (ref "R19") (pin "2") (pinfunction "2_2") (pintype "passive"))
      (node (ref "R20") (pin "2") (pinfunction "2_2") (pintype "passive"))
    )
    (net (code "76") (name "Net-(Q19-C)") (class "Default")
      (node (ref "Q19") (pin "3") (pinfunction "C_3") (pintype "passive"))
      (node (ref "R21") (pin "1") (pinfunction "1_1") (pintype "passive"))
    )
    (net (code "77") (name "Net-(Q20-B)") (class "Default")
      (node (ref "Q20") (pin "2") (pinfunction "B_2") (pintype "passive"))
      (node (ref "R23") (pin "2") (pinfunction "2_2") (pintype "passive"))
      (node (ref "R24") (pin "2") (pinfunction "2_2") (pintype "passive"))
    )
    (net (code "78") (name "Net-(Q20-C)") (class "Default")
      (node (ref "Q20") (pin "3") (pinfunction "C_3") (pintype "passive"))
      (node (ref "R25") (pin "1") (pinfunction "1_1") (pintype "passive"))
    )
    (net (code "79") (name "Net-(Q21-B)") (class "Default")
      (node (ref "Q21") (pin "2") (pinfunction "B_2") (pintype "passive"))
      (node (ref "R27") (pin "2") (pinfunction "2_2") (pintype "passive"))
      (node (ref "R28") (pin "2") (pinfunction "2_2") (pintype "passive"))
    )
    (net (code "80") (name "Net-(Q21-C)") (class "Default")
      (node (ref "Q21") (pin "3") (pinfunction "C_3") (pintype "passive"))
      (node (ref "R29") (pin "1") (pinfunction "1_1") (pintype "passive"))
    )
    (net (code "81") (name "Net-(Q22-B)") (class "Default")
      (node (ref "Q22") (pin "2") (pinfunction "B_2") (pintype "passive"))
      (node (ref "R31") (pin "2") (pinfunction "2_2") (pintype "passive"))
      (node (ref "R32") (pin "2") (pinfunction "2_2") (pintype "passive"))
    )
    (net (code "82") (name "Net-(Q22-C)") (class "Default")
      (node (ref "Q22") (pin "3") (pinfunction "C_3") (pintype "passive"))
      (node (ref "R33") (pin "1") (pinfunction "1_1") (pintype "passive"))
    )
    (net (code "83") (name "Net-(Q23-B)") (class "Default")
      (node (ref "Q23") (pin "2") (pinfunction "B_2") (pintype "passive"))
      (node (ref "R35") (pin "2") (pinfunction "2_2") (pintype "passive"))
      (node (ref "R36") (pin "2") (pinfunction "2_2") (pintype "passive"))
    )
    (net (code "84") (name "Net-(Q23-C)") (class "Default")
      (node (ref "Q23") (pin "3") (pinfunction "C_3") (pintype "passive"))
      (node (ref "R37") (pin "1") (pinfunction "1_1") (pintype "passive"))
    )
    (net (code "85") (name "Net-(Q24-B)") (class "Default")
      (node (ref "Q24") (pin "2") (pinfunction "B_2") (pintype "passive"))
      (node (ref "R39") (pin "2") (pinfunction "2_2") (pintype "passive"))
      (node (ref "R40") (pin "2") (pinfunction "2_2") (pintype "passive"))
    )
    (net (code "86") (name "Net-(Q24-C)") (class "Default")
      (node (ref "Q24") (pin "3") (pinfunction "C_3") (pintype "passive"))
      (node (ref "R41") (pin "1") (pinfunction "1_1") (pintype "passive"))
    )
    (net (code "87") (name "Net-(R43-PadA)") (class "Default")
      (node (ref "R43") (pin "A") (pinfunction "A_A") (pintype "passive"))
      (node (ref "R6") (pin "2") (pinfunction "2_2") (pintype "passive"))
    )
    (net (code "88") (name "Net-(R43-PadE)") (class "Default")
      (node (ref "R43") (pin "E") (pinfunction "E_E") (pintype "passive"))
      (node (ref "R5") (pin "1") (pinfunction "1_1") (pintype "passive"))
    )
    (net (code "89") (name "VDD") (class "Default")
      (node (ref "R42") (pin "1") (pinfunction "1_1") (pintype "passive"))
      (node (ref "R44") (pin "1") (pinfunction "1_1") (pintype "passive"))
      (node (ref "R45") (pin "1") (pinfunction "1_1") (pintype "passive"))
      (node (ref "R46") (pin "1") (pinfunction "1_1") (pintype "passive"))
      (node (ref "R47") (pin "1") (pinfunction "1_1") (pintype "passive"))
      (node (ref "R7") (pin "1") (pinfunction "1_1") (pintype "passive"))
    )
    (net (code "90") (name "VSS") (class "Default")
      (node (ref "C1") (pin "-") (pinfunction "-_-") (pintype "passive"))
      (node (ref "C2") (pin "-") (pinfunction "-_-") (pintype "passive"))
      (node (ref "C3") (pin "2") (pinfunction "2_2") (pintype "passive"))
      (node (ref "C4") (pin "2") (pinfunction "2_2") (pintype "passive"))
      (node (ref "IC2") (pin "1") (pinfunction "GND_1") (pintype "power_in"))
      (node (ref "LED1") (pin "C") (pinfunction "C_C") (pintype "passive"))
      (node (ref "LED2") (pin "C") (pinfunction "C_C") (pintype "passive"))
      (node (ref "LED3") (pin "C") (pinfunction "C_C") (pintype "passive"))
      (node (ref "LED4") (pin "C") (pinfunction "C_C") (pintype "passive"))
      (node (ref "LED5") (pin "C") (pinfunction "C_C") (pintype "passive"))
      (node (ref "LED6") (pin "C") (pinfunction "C_C") (pintype "passive"))
      (node (ref "PAD13") (pin "1") (pinfunction "P_1") (pintype "passive"))
      (node (ref "Q10") (pin "1") (pinfunction "E_1") (pintype "passive"))
      (node (ref "Q11") (pin "1") (pinfunction "E_1") (pintype "passive"))
      (node (ref "Q12") (pin "1") (pinfunction "E_1") (pintype "passive"))
      (node (ref "Q13") (pin "1") (pinfunction "E_1") (pintype "passive"))
      (node (ref "Q14") (pin "1") (pinfunction "E_1") (pintype "passive"))
      (node (ref "Q15") (pin "1") (pinfunction "E_1") (pintype "passive"))
      (node (ref "Q16") (pin "1") (pinfunction "E_1") (pintype "passive"))
      (node (ref "Q17") (pin "1") (pinfunction "E_1") (pintype "passive"))
      (node (ref "Q18") (pin "1") (pinfunction "E_1") (pintype "passive"))
      (node (ref "Q2") (pin "1") (pinfunction "E_1") (pintype "passive"))
      (node (ref "Q25") (pin "S") (pinfunction "S_S") (pintype "passive"))
      (node (ref "Q3") (pin "1") (pinfunction "E_1") (pintype "passive"))
      (node (ref "Q4") (pin "1") (pinfunction "E_1") (pintype "passive"))
      (node (ref "Q5") (pin "1") (pinfunction "E_1") (pintype "passive"))
      (node (ref "Q6") (pin "1") (pinfunction "E_1") (pintype "passive"))
      (node (ref "Q7") (pin "1") (pinfunction "E_1") (pintype "passive"))
      (node (ref "Q8") (pin "1") (pinfunction "E_1") (pintype "passive"))
      (node (ref "Q9") (pin "1") (pinfunction "E_1") (pintype "passive"))
      (node (ref "R6") (pin "1") (pinfunction "1_1") (pintype "passive"))
    )
  )
)
